# low-gain-radio.net
KiCad netlist of a schematic drawn in EAGLE
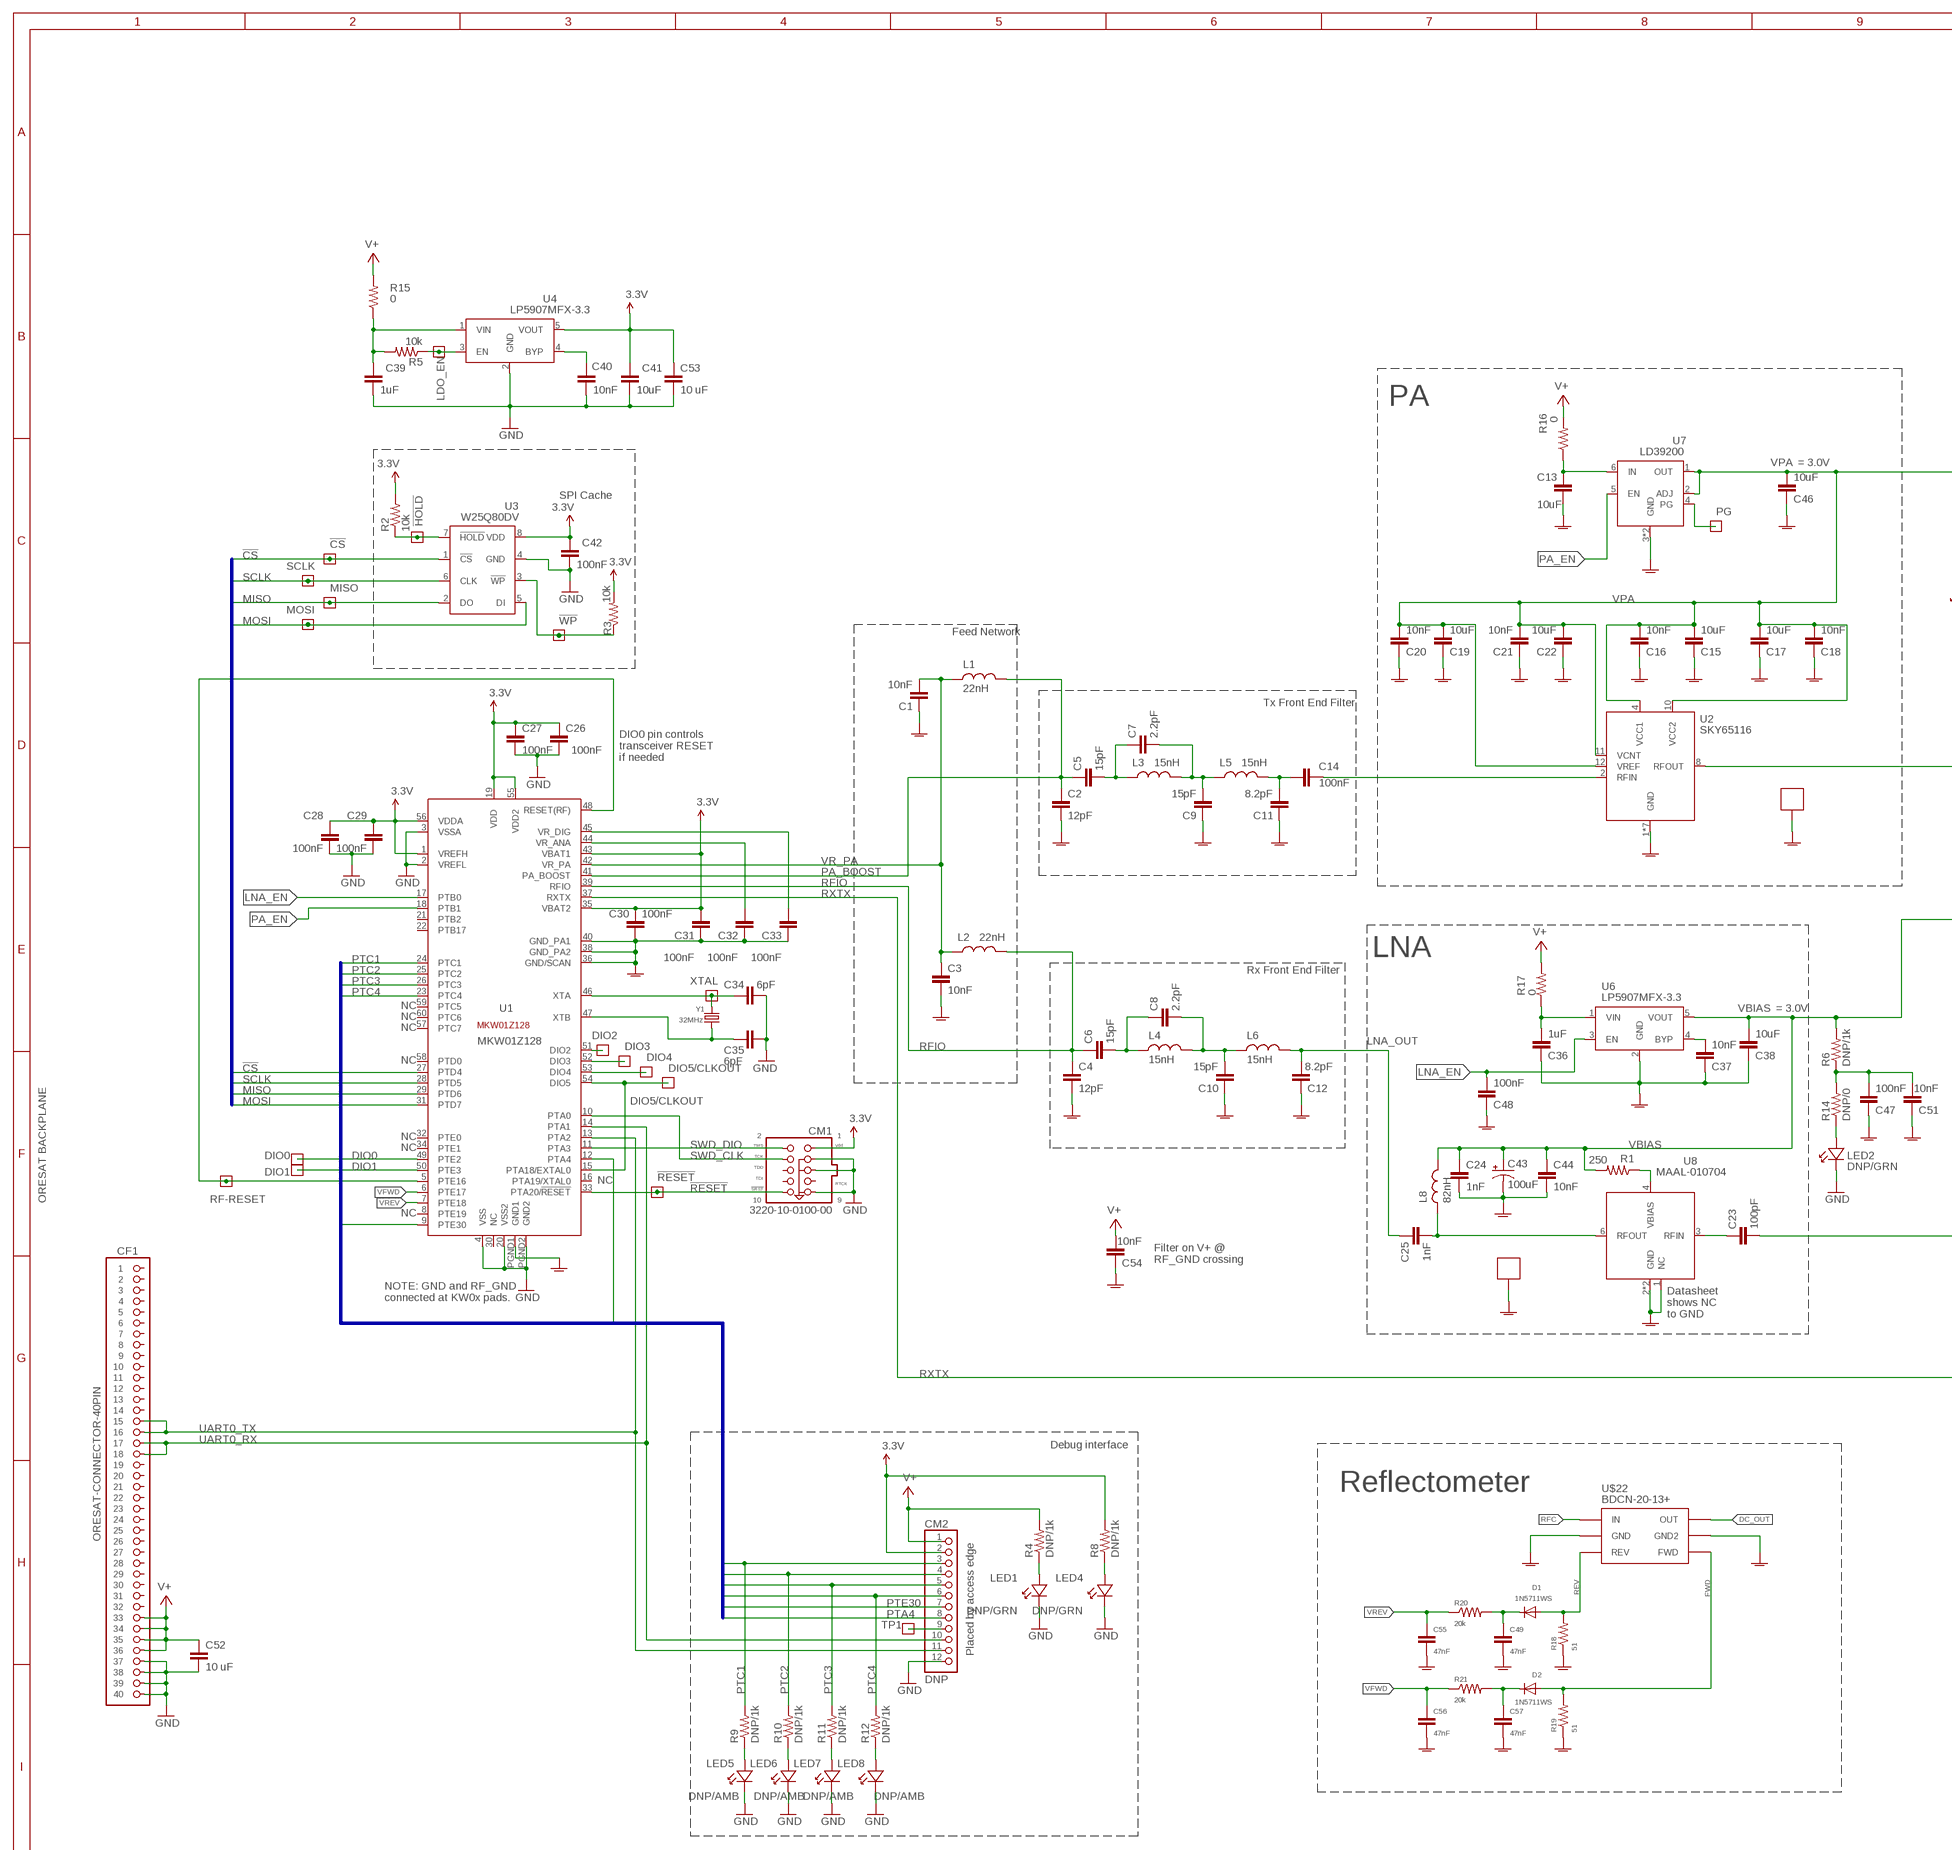
[diagram p0: schematic, sheet 1, part 1 of 2]
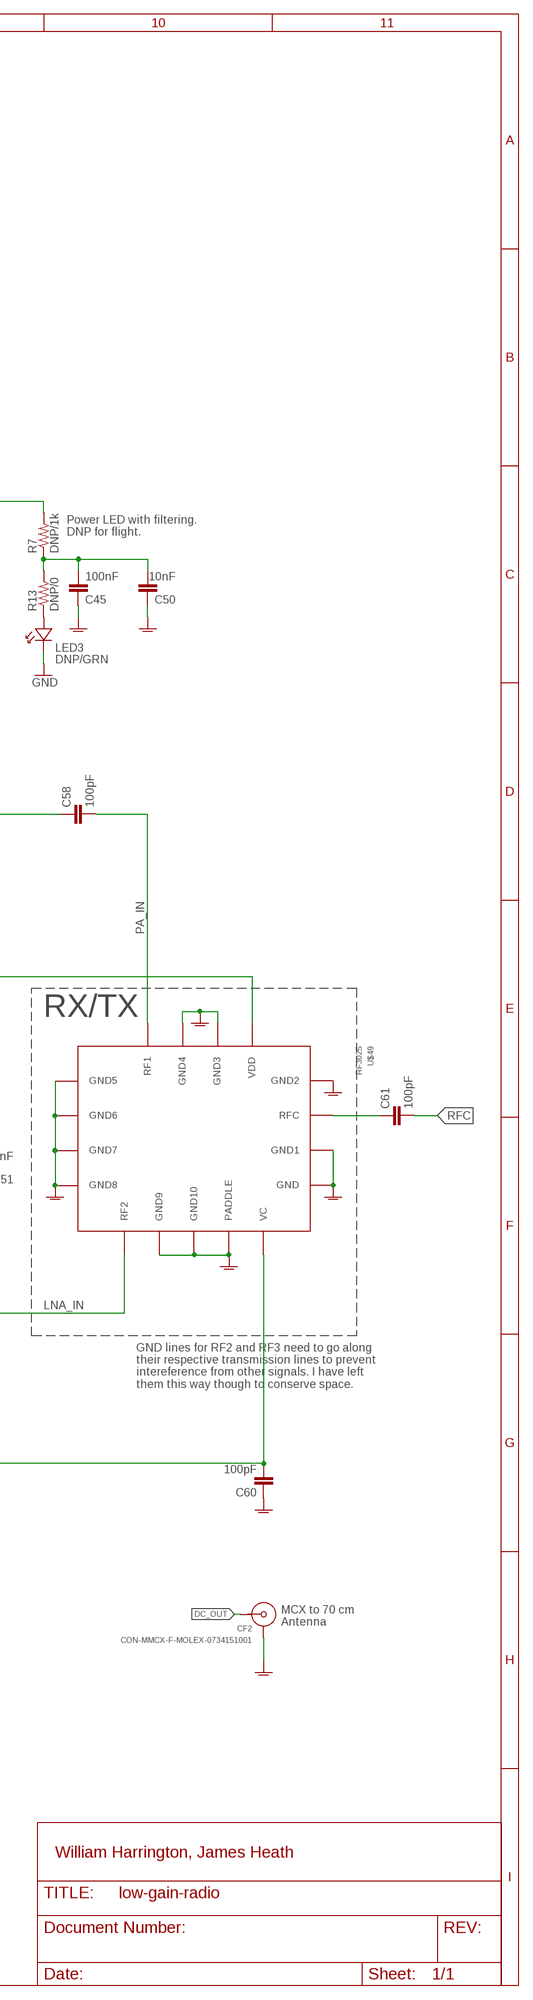
[diagram p1: schematic, sheet 1, part 2 of 2]

(export (version "E")
  (design (tool "Eeschema 10.0.6"))
  (components
    (comp (ref "!CS")
      (value "TEST-POINT")
      (footprint "eagle-import:2MM-TEST-POINT")
      (libsource (lib "eagle-import") (part "TEST-POINT"))
    )
    (comp (ref "!HOLD")
      (value "TEST-POINT")
      (footprint "eagle-import:2MM-TEST-POINT")
      (libsource (lib "eagle-import") (part "TEST-POINT"))
    )
    (comp (ref "!RESET")
      (value "TEST-POINT")
      (footprint "eagle-import:2MM-TEST-POINT")
      (libsource (lib "eagle-import") (part "TEST-POINT"))
    )
    (comp (ref "!WP")
      (value "TEST-POINT")
      (footprint "eagle-import:2MM-TEST-POINT")
      (libsource (lib "eagle-import") (part "TEST-POINT"))
    )
    (comp (ref "C1")
      (value "10nF")
      (footprint "eagle-import:.0603-B-NOSILK")
      (fields (field (name "MFG") "Murata"))
      (libsource (lib "eagle-import") (part "rcl_custom_C-EU0603-B-NOSILK"))
    )
    (comp (ref "C2")
      (value "12pF")
      (footprint "eagle-import:.0603-B-NOSILK")
      (fields (field (name "MFG") "Murata"))
      (libsource (lib "eagle-import") (part "rcl_custom_C-EU0603-B-NOSILK"))
    )
    (comp (ref "C3")
      (value "10nF")
      (footprint "eagle-import:.0603-B-NOSILK")
      (fields (field (name "MFG") "Murata"))
      (libsource (lib "eagle-import") (part "rcl_custom_C-EU0603-B-NOSILK"))
    )
    (comp (ref "C4")
      (value "12pF")
      (footprint "eagle-import:.0603-B-NOSILK")
      (fields (field (name "MFG") "Murata"))
      (libsource (lib "eagle-import") (part "rcl_custom_C-EU0603-B-NOSILK"))
    )
    (comp (ref "C5")
      (value "15pF")
      (footprint "eagle-import:.0603-B-NOSILK")
      (fields (field (name "MFG") "Murata"))
      (libsource (lib "eagle-import") (part "rcl_custom_C-EU0603-B-NOSILK"))
    )
    (comp (ref "C6")
      (value "15pF")
      (footprint "eagle-import:.0603-B-NOSILK")
      (fields (field (name "MFG") "Murata"))
      (libsource (lib "eagle-import") (part "rcl_custom_C-EU0603-B-NOSILK"))
    )
    (comp (ref "C7")
      (value "2.2pF")
      (footprint "eagle-import:.0603-B-NOSILK")
      (fields (field (name "MFG") "Murata"))
      (libsource (lib "eagle-import") (part "rcl_custom_C-EU0603-B-NOSILK"))
    )
    (comp (ref "C8")
      (value "2.2pF")
      (footprint "eagle-import:.0603-B-NOSILK")
      (fields (field (name "MFG") "Murata"))
      (libsource (lib "eagle-import") (part "rcl_custom_C-EU0603-B-NOSILK"))
    )
    (comp (ref "C9")
      (value "15pF")
      (footprint "eagle-import:.0603-B-NOSILK")
      (fields (field (name "MFG") "Murata"))
      (libsource (lib "eagle-import") (part "rcl_custom_C-EU0603-B-NOSILK"))
    )
    (comp (ref "C10")
      (value "15pF")
      (footprint "eagle-import:.0603-B-NOSILK")
      (fields (field (name "MFG") "Murata"))
      (libsource (lib "eagle-import") (part "rcl_custom_C-EU0603-B-NOSILK"))
    )
    (comp (ref "C11")
      (value "8.2pF")
      (footprint "eagle-import:.0603-B-NOSILK")
      (fields (field (name "MFG") "AVX"))
      (libsource (lib "eagle-import") (part "rcl_custom_C-EU0603-B-NOSILK"))
    )
    (comp (ref "C12")
      (value "8.2pF")
      (footprint "eagle-import:.0603-B-NOSILK")
      (fields (field (name "MFG") "AVX"))
      (libsource (lib "eagle-import") (part "rcl_custom_C-EU0603-B-NOSILK"))
    )
    (comp (ref "C13")
      (value "10uF")
      (footprint "eagle-import:.0603-B-NOSILK")
      (fields (field (name "MFG") "Murata"))
      (libsource (lib "eagle-import") (part "rcl_custom_C-EU0603-B-NOSILK"))
    )
    (comp (ref "C14")
      (value "100nF")
      (footprint "eagle-import:.0603-B-NOSILK")
      (fields (field (name "MFG") "AVX"))
      (libsource (lib "eagle-import") (part "rcl_custom_C-EU0603-B-NOSILK"))
    )
    (comp (ref "C15")
      (value "10uF")
      (footprint "eagle-import:.0603-B-NOSILK")
      (fields (field (name "MFG") "Murata"))
      (libsource (lib "eagle-import") (part "rcl_custom_C-EU0603-B-NOSILK"))
    )
    (comp (ref "C16")
      (value "10nF")
      (footprint "eagle-import:.0603-B-NOSILK")
      (fields (field (name "MFG") "Murata"))
      (libsource (lib "eagle-import") (part "rcl_custom_C-EU0603-B-NOSILK"))
    )
    (comp (ref "C17")
      (value "10uF")
      (footprint "eagle-import:.0603-B-NOSILK")
      (fields (field (name "MFG") "Murata"))
      (libsource (lib "eagle-import") (part "rcl_custom_C-EU0603-B-NOSILK"))
    )
    (comp (ref "C18")
      (value "10nF")
      (footprint "eagle-import:.0603-B-NOSILK")
      (fields (field (name "MFG") "Murata"))
      (libsource (lib "eagle-import") (part "rcl_custom_C-EU0603-B-NOSILK"))
    )
    (comp (ref "C19")
      (value "10uF")
      (footprint "eagle-import:.0603-B-NOSILK")
      (fields (field (name "MFG") "Murata"))
      (libsource (lib "eagle-import") (part "rcl_custom_C-EU0603-B-NOSILK"))
    )
    (comp (ref "C20")
      (value "10nF")
      (footprint "eagle-import:.0603-B-NOSILK")
      (fields (field (name "MFG") "Murata"))
      (libsource (lib "eagle-import") (part "rcl_custom_C-EU0603-B-NOSILK"))
    )
    (comp (ref "C21")
      (value "10nF")
      (footprint "eagle-import:.0603-B-NOSILK")
      (fields (field (name "MFG") "Murata"))
      (libsource (lib "eagle-import") (part "rcl_custom_C-EU0603-B-NOSILK"))
    )
    (comp (ref "C22")
      (value "10uF")
      (footprint "eagle-import:.0603-B-NOSILK")
      (fields (field (name "MFG") "Murata"))
      (libsource (lib "eagle-import") (part "rcl_custom_C-EU0603-B-NOSILK"))
    )
    (comp (ref "C23")
      (value "100pF")
      (footprint "eagle-import:.0402-C-NOSILK")
      (fields (field (name "MFG") "Kemet") (field (name "MPN") "CBR04C101F3GAC"))
      (libsource (lib "eagle-import") (part "C-EU0402-C-NOSILK"))
    )
    (comp (ref "C24")
      (value "1nF")
      (footprint "eagle-import:.0402-B-NOSILK")
      (fields (field (name "MFG") "Murata"))
      (libsource (lib "eagle-import") (part "rcl_custom_C-EU0402-B-NOSILK"))
    )
    (comp (ref "C25")
      (value "1nF")
      (footprint "eagle-import:.0402-B-NOSILK")
      (fields (field (name "MFG") "Murata"))
      (libsource (lib "eagle-import") (part "rcl_custom_C-EU0402-B-NOSILK"))
    )
    (comp (ref "C26")
      (value "100nF")
      (footprint "eagle-import:.0603-B-NOSILK")
      (fields (field (name "MFG") "AVX"))
      (libsource (lib "eagle-import") (part "rcl_custom_C-EU0603-B-NOSILK"))
    )
    (comp (ref "C27")
      (value "100nF")
      (footprint "eagle-import:.0603-B-NOSILK")
      (fields (field (name "MFG") "AVX"))
      (libsource (lib "eagle-import") (part "rcl_custom_C-EU0603-B-NOSILK"))
    )
    (comp (ref "C28")
      (value "100nF")
      (footprint "eagle-import:.0603-B-NOSILK")
      (fields (field (name "MFG") "AVX"))
      (libsource (lib "eagle-import") (part "rcl_custom_C-EU0603-B-NOSILK"))
    )
    (comp (ref "C29")
      (value "100nF")
      (footprint "eagle-import:.0603-B-NOSILK")
      (fields (field (name "MFG") "AVX"))
      (libsource (lib "eagle-import") (part "rcl_custom_C-EU0603-B-NOSILK"))
    )
    (comp (ref "C30")
      (value "100nF")
      (footprint "eagle-import:.0603-B-NOSILK")
      (fields (field (name "MFG") "AVX"))
      (libsource (lib "eagle-import") (part "rcl_custom_C-EU0603-B-NOSILK"))
    )
    (comp (ref "C31")
      (value "100nF")
      (footprint "eagle-import:.0603-B-NOSILK")
      (fields (field (name "MFG") "AVX"))
      (libsource (lib "eagle-import") (part "rcl_custom_C-EU0603-B-NOSILK"))
    )
    (comp (ref "C32")
      (value "100nF")
      (footprint "eagle-import:.0603-B-NOSILK")
      (fields (field (name "MFG") "AVX"))
      (libsource (lib "eagle-import") (part "rcl_custom_C-EU0603-B-NOSILK"))
    )
    (comp (ref "C33")
      (value "100nF")
      (footprint "eagle-import:.0603-B-NOSILK")
      (fields (field (name "MFG") "AVX"))
      (libsource (lib "eagle-import") (part "rcl_custom_C-EU0603-B-NOSILK"))
    )
    (comp (ref "C34")
      (value "6pF")
      (footprint "eagle-import:.0603-B-NOSILK")
      (fields (field (name "MFG") "Murata"))
      (libsource (lib "eagle-import") (part "rcl_custom_C-EU0603-B-NOSILK"))
    )
    (comp (ref "C35")
      (value "6pF")
      (footprint "eagle-import:.0603-B-NOSILK")
      (fields (field (name "MFG") "Murata"))
      (libsource (lib "eagle-import") (part "rcl_custom_C-EU0603-B-NOSILK"))
    )
    (comp (ref "C36")
      (value "1uF")
      (footprint "eagle-import:.0603-B-NOSILK")
      (fields (field (name "MFG") "Murata"))
      (libsource (lib "eagle-import") (part "rcl_custom_C-EU0603-B-NOSILK"))
    )
    (comp (ref "C37")
      (value "10nF")
      (footprint "eagle-import:.0603-B-NOSILK")
      (fields (field (name "MFG") "Murata"))
      (libsource (lib "eagle-import") (part "rcl_custom_C-EU0603-B-NOSILK"))
    )
    (comp (ref "C38")
      (value "10uF")
      (footprint "eagle-import:.0603-B-NOSILK")
      (fields (field (name "MFG") "Murata"))
      (libsource (lib "eagle-import") (part "rcl_custom_C-EU0603-B-NOSILK"))
    )
    (comp (ref "C39")
      (value "1uF")
      (footprint "eagle-import:.0603-B-NOSILK")
      (fields (field (name "MFG") "Murata"))
      (libsource (lib "eagle-import") (part "rcl_custom_C-EU0603-B-NOSILK"))
    )
    (comp (ref "C40")
      (value "10nF")
      (footprint "eagle-import:.0603-B-NOSILK")
      (fields (field (name "MFG") "Murata"))
      (libsource (lib "eagle-import") (part "rcl_custom_C-EU0603-B-NOSILK"))
    )
    (comp (ref "C41")
      (value "10uF")
      (footprint "eagle-import:.0603-B-NOSILK")
      (fields (field (name "MFG") "Murata"))
      (libsource (lib "eagle-import") (part "rcl_custom_C-EU0603-B-NOSILK"))
    )
    (comp (ref "C42")
      (value "100nF")
      (footprint "eagle-import:.0603-B-NOSILK")
      (fields (field (name "MFG") "AVX"))
      (libsource (lib "eagle-import") (part "rcl_custom_C-EU0603-B-NOSILK"))
    )
    (comp (ref "C43")
      (value "100uF")
      (footprint "eagle-import:CT6032")
      (fields (field (name "MFG") "AVX"))
      (libsource (lib "eagle-import") (part "CPOL-USCT6032"))
    )
    (comp (ref "C44")
      (value "10nF")
      (footprint "eagle-import:.0402-B-NOSILK")
      (fields (field (name "MFG") "Murata"))
      (libsource (lib "eagle-import") (part "rcl_custom_C-EU0402-B-NOSILK"))
    )
    (comp (ref "C45")
      (value "100nF")
      (footprint "eagle-import:.0603-B-NOSILK")
      (fields (field (name "MFG") "AVX"))
      (libsource (lib "eagle-import") (part "rcl_custom_C-EU0603-B-NOSILK"))
    )
    (comp (ref "C46")
      (value "10uF")
      (footprint "eagle-import:.0603-B-NOSILK")
      (fields (field (name "MFG") "Murata"))
      (libsource (lib "eagle-import") (part "rcl_custom_C-EU0603-B-NOSILK"))
    )
    (comp (ref "C47")
      (value "100nF")
      (footprint "eagle-import:.0603-B-NOSILK")
      (fields (field (name "MFG") "AVX"))
      (libsource (lib "eagle-import") (part "rcl_custom_C-EU0603-B-NOSILK"))
    )
    (comp (ref "C48")
      (value "100nF")
      (footprint "eagle-import:.0603-B-NOSILK")
      (fields (field (name "MFG") "AVX"))
      (libsource (lib "eagle-import") (part "rcl_custom_C-EU0603-B-NOSILK"))
    )
    (comp (ref "C49")
      (value "47nF")
      (footprint "eagle-import:.0402-C-NOSILK")
      (fields (field (name "MFG") "Taiyo Yuden") (field (name "MPN") "LMK105SD472KV-F"))
      (libsource (lib "eagle-import") (part "C-EU0402-C-NOSILK"))
    )
    (comp (ref "C50")
      (value "10nF")
      (footprint "eagle-import:.0402-B-NOSILK")
      (fields (field (name "MFG") "Murata"))
      (libsource (lib "eagle-import") (part "rcl_custom_C-EU0402-B-NOSILK"))
    )
    (comp (ref "C51")
      (value "10nF")
      (footprint "eagle-import:.0402-B-NOSILK")
      (fields (field (name "MFG") "Murata"))
      (libsource (lib "eagle-import") (part "rcl_custom_C-EU0402-B-NOSILK"))
    )
    (comp (ref "C52")
      (value "10 uF")
      (footprint "eagle-import:.0805-B-NOSILK")
      (libsource (lib "eagle-import") (part "rcl_custom_C-EU0805-B-NOSILK"))
    )
    (comp (ref "C53")
      (value "10 uF")
      (footprint "eagle-import:.0805-B-NOSILK")
      (fields (field (name "MFG") "Murata"))
      (libsource (lib "eagle-import") (part "rcl_custom_C-EU0805-B-NOSILK"))
    )
    (comp (ref "C54")
      (value "10nF")
      (footprint "eagle-import:.0402-B-NOSILK")
      (fields (field (name "MFG") "Murata"))
      (libsource (lib "eagle-import") (part "rcl_custom_C-EU0402-B-NOSILK"))
    )
    (comp (ref "C55")
      (value "47nF")
      (footprint "eagle-import:.0402-C-NOSILK")
      (fields (field (name "MFG") "Taiyo Yuden") (field (name "MPN") "LMK105SD472KV-F"))
      (libsource (lib "eagle-import") (part "C-EU0402-C-NOSILK"))
    )
    (comp (ref "C56")
      (value "47nF")
      (footprint "eagle-import:.0402-C-NOSILK")
      (fields (field (name "MFG") "Taiyo Yuden") (field (name "MPN") "LMK105SD472KV-F"))
      (libsource (lib "eagle-import") (part "C-EU0402-C-NOSILK"))
    )
    (comp (ref "C57")
      (value "47nF")
      (footprint "eagle-import:.0402-C-NOSILK")
      (fields (field (name "MFG") "Taiyo Yuden") (field (name "MPN") "LMK105SD472KV-F"))
      (libsource (lib "eagle-import") (part "C-EU0402-C-NOSILK"))
    )
    (comp (ref "C58")
      (value "100pF")
      (footprint "eagle-import:.0402-C-NOSILK")
      (fields (field (name "MFG") "Kemet") (field (name "MPN") "CBR04C101F3GAC"))
      (libsource (lib "eagle-import") (part "C-EU0402-C-NOSILK"))
    )
    (comp (ref "C60")
      (value "100pF")
      (footprint "eagle-import:.0402-C-NOSILK")
      (fields (field (name "MFG") "Kemet") (field (name "MPN") "CBR04C101F3GAC"))
      (libsource (lib "eagle-import") (part "C-EU0402-C-NOSILK"))
    )
    (comp (ref "C61")
      (value "100pF")
      (footprint "eagle-import:.0402-C-NOSILK")
      (fields (field (name "MFG") "Kemet") (field (name "MPN") "CBR04C101F3GAC"))
      (libsource (lib "eagle-import") (part "C-EU0402-C-NOSILK"))
    )
    (comp (ref "CF1")
      (value "ORESAT-CONNECTOR-40PIN")
      (footprint "eagle-import:HARWIN-ARCHER-M50-3202045")
      (libsource (lib "eagle-import") (part "ORESAT-CONNECTOR-40PIN"))
    )
    (comp (ref "CF2")
      (value "CON-MMCX-F-MOLEX-0734151001")
      (footprint "eagle-import:CON-MMCX-F-MOLEX-0734151001")
      (libsource (lib "eagle-import") (part "CON-MMCX-F-MOLEX-0734151001"))
    )
    (comp (ref "CM1")
      (value "3220-10-0100-00")
      (footprint "eagle-import:PINHEADER-2X5-0.05+POL+SILK")
      (fields (field (name "MFG") "CNC Tech"))
      (libsource (lib "eagle-import") (part "JTAG_ARM-10-50MIL"))
    )
    (comp (ref "CM2")
      (value "DNP")
      (footprint "eagle-import:1X12")
      (libsource (lib "eagle-import") (part "PINHD-1X12"))
    )
    (comp (ref "D1")
      (value "1N5711WS")
      (footprint "eagle-import:SOD-323")
      (fields (field (name "MFG") "Diodes Incorporated"))
      (libsource (lib "eagle-import") (part "DIODESOD-323"))
    )
    (comp (ref "D2")
      (value "1N5711WS")
      (footprint "eagle-import:SOD-323")
      (fields (field (name "MFG") "Diodes Incorporated"))
      (libsource (lib "eagle-import") (part "DIODESOD-323"))
    )
    (comp (ref "DIO0")
      (value "TEST-POINT")
      (footprint "eagle-import:2MM-TEST-POINT")
      (libsource (lib "eagle-import") (part "TEST-POINT"))
    )
    (comp (ref "DIO1")
      (value "TEST-POINT")
      (footprint "eagle-import:2MM-TEST-POINT")
      (libsource (lib "eagle-import") (part "TEST-POINT"))
    )
    (comp (ref "DIO2")
      (value "TEST-POINT")
      (footprint "eagle-import:2MM-TEST-POINT")
      (libsource (lib "eagle-import") (part "TEST-POINT"))
    )
    (comp (ref "DIO3")
      (value "TEST-POINT")
      (footprint "eagle-import:2MM-TEST-POINT")
      (libsource (lib "eagle-import") (part "TEST-POINT"))
    )
    (comp (ref "DIO4")
      (value "TEST-POINT")
      (footprint "eagle-import:2MM-TEST-POINT")
      (libsource (lib "eagle-import") (part "TEST-POINT"))
    )
    (comp (ref "DIO5/CLKOUT")
      (value "TEST-POINT")
      (footprint "eagle-import:2MM-TEST-POINT")
      (libsource (lib "eagle-import") (part "TEST-POINT"))
    )
    (comp (ref "L1")
      (value "22nH")
      (footprint "eagle-import:.0603-B-NOSILK@1")
      (fields (field (name "MFG") "Murata"))
      (libsource (lib "eagle-import") (part "L-US0603-B-NOSILK"))
    )
    (comp (ref "L2")
      (value "22nH")
      (footprint "eagle-import:.0603-B-NOSILK@1")
      (fields (field (name "MFG") "Murata"))
      (libsource (lib "eagle-import") (part "L-US0603-B-NOSILK"))
    )
    (comp (ref "L3")
      (value "15nH")
      (footprint "eagle-import:.0603-B-NOSILK@1")
      (fields (field (name "MFG") "Murata"))
      (libsource (lib "eagle-import") (part "L-US0603-B-NOSILK"))
    )
    (comp (ref "L4")
      (value "15nH")
      (footprint "eagle-import:.0603-B-NOSILK@1")
      (fields (field (name "MFG") "Murata"))
      (libsource (lib "eagle-import") (part "L-US0603-B-NOSILK"))
    )
    (comp (ref "L5")
      (value "15nH")
      (footprint "eagle-import:.0603-B-NOSILK@1")
      (fields (field (name "MFG") "Murata"))
      (libsource (lib "eagle-import") (part "L-US0603-B-NOSILK"))
    )
    (comp (ref "L6")
      (value "15nH")
      (footprint "eagle-import:.0603-B-NOSILK@1")
      (fields (field (name "MFG") "Murata"))
      (libsource (lib "eagle-import") (part "L-US0603-B-NOSILK"))
    )
    (comp (ref "L8")
      (value "82nH")
      (footprint "eagle-import:.0603-B-NOSILK@1")
      (fields (field (name "MFG") "Murata"))
      (libsource (lib "eagle-import") (part "L-US0603-B-NOSILK"))
    )
    (comp (ref "LDO_EN")
      (value "TEST-POINT")
      (footprint "eagle-import:2MM-TEST-POINT")
      (libsource (lib "eagle-import") (part "TEST-POINT"))
    )
    (comp (ref "LED1")
      (value "DNP/GRN")
      (footprint "eagle-import:LED-0603")
      (fields (field (name "MFG") "Lite-On Inc."))
      (libsource (lib "eagle-import") (part "LED-0603"))
    )
    (comp (ref "LED2")
      (value "DNP/GRN")
      (footprint "eagle-import:LED-0603")
      (fields (field (name "MFG") "Lite-On Inc."))
      (libsource (lib "eagle-import") (part "LED-0603"))
    )
    (comp (ref "LED3")
      (value "DNP/GRN")
      (footprint "eagle-import:LED-0603")
      (fields (field (name "MFG") "Lite-On Inc."))
      (libsource (lib "eagle-import") (part "LED-0603"))
    )
    (comp (ref "LED4")
      (value "DNP/GRN")
      (footprint "eagle-import:LED-0603")
      (fields (field (name "MFG") "Lite-On Inc."))
      (libsource (lib "eagle-import") (part "LED-0603"))
    )
    (comp (ref "LED5")
      (value "DNP/AMB")
      (footprint "eagle-import:LED-0603")
      (fields (field (name "MFG") "Lite-On Inc."))
      (libsource (lib "eagle-import") (part "LED-0603"))
    )
    (comp (ref "LED6")
      (value "DNP/AMB")
      (footprint "eagle-import:LED-0603")
      (fields (field (name "MFG") "Lite-On Inc."))
      (libsource (lib "eagle-import") (part "LED-0603"))
    )
    (comp (ref "LED7")
      (value "DNP/AMB")
      (footprint "eagle-import:LED-0603")
      (fields (field (name "MFG") "Lite-On Inc."))
      (libsource (lib "eagle-import") (part "LED-0603"))
    )
    (comp (ref "LED8")
      (value "DNP/AMB")
      (footprint "eagle-import:LED-0603")
      (fields (field (name "MFG") "Lite-On Inc."))
      (libsource (lib "eagle-import") (part "LED-0603"))
    )
    (comp (ref "MISO")
      (value "TEST-POINT")
      (footprint "eagle-import:2MM-TEST-POINT")
      (libsource (lib "eagle-import") (part "TEST-POINT"))
    )
    (comp (ref "MOSI")
      (value "TEST-POINT")
      (footprint "eagle-import:2MM-TEST-POINT")
      (libsource (lib "eagle-import") (part "TEST-POINT"))
    )
    (comp (ref "PG")
      (value "TEST-POINT")
      (footprint "eagle-import:2MM-TEST-POINT")
      (libsource (lib "eagle-import") (part "TEST-POINT"))
    )
    (comp (ref "R1")
      (value "250")
      (footprint "eagle-import:.0603-B-NOSILK@1")
      (fields (field (name "MFG") "Samsung"))
      (libsource (lib "eagle-import") (part "rcl_custom_R-US_0603-B-NOSILK"))
    )
    (comp (ref "R2")
      (value "10k")
      (footprint "eagle-import:.0603-B-NOSILK@1")
      (fields (field (name "MFG") "Yageo"))
      (libsource (lib "eagle-import") (part "rcl_custom_R-US_0603-B-NOSILK"))
    )
    (comp (ref "R3")
      (value "10k")
      (footprint "eagle-import:.0603-B-NOSILK@1")
      (fields (field (name "MFG") "Yageo"))
      (libsource (lib "eagle-import") (part "rcl_custom_R-US_0603-B-NOSILK"))
    )
    (comp (ref "R4")
      (value "DNP/1k")
      (footprint "eagle-import:.0603-B-NOSILK@1")
      (fields (field (name "MFG") "Yageo"))
      (libsource (lib "eagle-import") (part "rcl_custom_R-US_0603-B-NOSILK"))
    )
    (comp (ref "R5")
      (value "10k")
      (footprint "eagle-import:.0603-B-NOSILK@1")
      (fields (field (name "MFG") "Yageo"))
      (libsource (lib "eagle-import") (part "rcl_custom_R-US_0603-B-NOSILK"))
    )
    (comp (ref "R6")
      (value "DNP/1k")
      (footprint "eagle-import:.0603-B-NOSILK@1")
      (fields (field (name "MFG") "Yageo"))
      (libsource (lib "eagle-import") (part "rcl_custom_R-US_0603-B-NOSILK"))
    )
    (comp (ref "R7")
      (value "DNP/1k")
      (footprint "eagle-import:.0603-B-NOSILK@1")
      (fields (field (name "MFG") "Yageo"))
      (libsource (lib "eagle-import") (part "rcl_custom_R-US_0603-B-NOSILK"))
    )
    (comp (ref "R8")
      (value "DNP/1k")
      (footprint "eagle-import:.0603-B-NOSILK@1")
      (fields (field (name "MFG") "Yageo"))
      (libsource (lib "eagle-import") (part "rcl_custom_R-US_0603-B-NOSILK"))
    )
    (comp (ref "R9")
      (value "DNP/1k")
      (footprint "eagle-import:.0603-B-NOSILK@1")
      (fields (field (name "MFG") "Yageo"))
      (libsource (lib "eagle-import") (part "rcl_custom_R-US_0603-B-NOSILK"))
    )
    (comp (ref "R10")
      (value "DNP/1k")
      (footprint "eagle-import:.0603-B-NOSILK@1")
      (fields (field (name "MFG") "Yageo"))
      (libsource (lib "eagle-import") (part "rcl_custom_R-US_0603-B-NOSILK"))
    )
    (comp (ref "R11")
      (value "DNP/1k")
      (footprint "eagle-import:.0603-B-NOSILK@1")
      (fields (field (name "MFG") "Yageo"))
      (libsource (lib "eagle-import") (part "rcl_custom_R-US_0603-B-NOSILK"))
    )
    (comp (ref "R12")
      (value "DNP/1k")
      (footprint "eagle-import:.0603-B-NOSILK@1")
      (fields (field (name "MFG") "Yageo"))
      (libsource (lib "eagle-import") (part "rcl_custom_R-US_0603-B-NOSILK"))
    )
    (comp (ref "R13")
      (value "DNP/0")
      (footprint "eagle-import:.0603-B-NOSILK@1")
      (fields (field (name "MFG") "Yageo"))
      (libsource (lib "eagle-import") (part "rcl_custom_R-US_0603-B-NOSILK"))
    )
    (comp (ref "R14")
      (value "DNP/0")
      (footprint "eagle-import:.0603-B-NOSILK@1")
      (fields (field (name "MFG") "Yageo"))
      (libsource (lib "eagle-import") (part "rcl_custom_R-US_0603-B-NOSILK"))
    )
    (comp (ref "R15")
      (value "0")
      (footprint "eagle-import:.0805-C-NOSILK$1")
      (fields (field (name "MFG") "Yageo") (field (name "MPN") "RC0805JR-070RL"))
      (libsource (lib "eagle-import") (part "R-US_0805-C-NOSILK"))
    )
    (comp (ref "R16")
      (value "0")
      (footprint "eagle-import:.0805-C-NOSILK$1")
      (fields (field (name "MFG") "Yageo") (field (name "MPN") "RC0805JR-070RL"))
      (libsource (lib "eagle-import") (part "R-US_0805-C-NOSILK"))
    )
    (comp (ref "R17")
      (value "0")
      (footprint "eagle-import:.0805-C-NOSILK$1")
      (fields (field (name "MFG") "Yageo") (field (name "MPN") "RC0805JR-070RL"))
      (libsource (lib "eagle-import") (part "R-US_0805-C-NOSILK"))
    )
    (comp (ref "R18")
      (value "51")
      (footprint "eagle-import:.0402-C-NOSILK$1")
      (fields (field (name "MFG") "Yageo") (field (name "MPN") "RC0402FR-0751RL"))
      (libsource (lib "eagle-import") (part "R-US_0402-C-NOSILK"))
    )
    (comp (ref "R19")
      (value "51")
      (footprint "eagle-import:.0402-C-NOSILK$1")
      (fields (field (name "MFG") "Yageo") (field (name "MPN") "RC0402FR-0751RL"))
      (libsource (lib "eagle-import") (part "R-US_0402-C-NOSILK"))
    )
    (comp (ref "R20")
      (value "20k")
      (footprint "eagle-import:.0402-C-NOSILK$1")
      (fields (field (name "MFG") "Yageo") (field (name "MPN") "RT0402BRD0721KL"))
      (libsource (lib "eagle-import") (part "R-US_0402-C-NOSILK"))
    )
    (comp (ref "R21")
      (value "20k")
      (footprint "eagle-import:.0402-C-NOSILK$1")
      (fields (field (name "MFG") "Yageo") (field (name "MPN") "RT0402BRD0721KL"))
      (libsource (lib "eagle-import") (part "R-US_0402-C-NOSILK"))
    )
    (comp (ref "RF-RESET")
      (value "TEST-POINT")
      (footprint "eagle-import:2MM-TEST-POINT")
      (libsource (lib "eagle-import") (part "TEST-POINT"))
    )
    (comp (ref "SCLK")
      (value "TEST-POINT")
      (footprint "eagle-import:2MM-TEST-POINT")
      (libsource (lib "eagle-import") (part "TEST-POINT"))
    )
    (comp (ref "SH1")
      (value "BMI-S-202-SHIELD")
      (footprint "eagle-import:BMI-S-202")
      (libsource (lib "eagle-import") (part "BMI-S-202-SHIELD"))
    )
    (comp (ref "SH2")
      (value "BMI-S-202-SHIELD")
      (footprint "eagle-import:BMI-S-202")
      (libsource (lib "eagle-import") (part "BMI-S-202-SHIELD"))
    )
    (comp (ref "TP1")
      (value "TEST-POINT")
      (footprint "eagle-import:2MM-TEST-POINT")
      (libsource (lib "eagle-import") (part "TEST-POINT"))
    )
    (comp (ref "U$22")
      (value "BDCN-20-13+")
      (footprint "eagle-import:FV1206-1")
      (fields (field (name "MFG") "Mini-Circuits"))
      (libsource (lib "eagle-import") (part "BDCN-20-13+"))
    )
    (comp (ref "U$49")
      (value "RF3025")
      (footprint "eagle-import:QFN-16_3MMX3MM")
      (fields (field (name "MFG") "RFMD") (field (name "MPN") "RF3025TR7"))
      (libsource (lib "eagle-import") (part "RF3025"))
    )
    (comp (ref "U1")
      (value "MKW01Z128")
      (footprint "eagle-import:MKW01Z128")
      (fields (field (name "MPN") "MKW01Z128CHN"))
      (libsource (lib "eagle-import") (part "MKW01Z128"))
    )
    (comp (ref "U2")
      (value "SKY65116")
      (footprint "eagle-import:SKY65116")
      (libsource (lib "eagle-import") (part "SKY65116"))
    )
    (comp (ref "U3")
      (value "W25Q80DV")
      (footprint "eagle-import:W25Q80DV")
      (fields (field (name "MFG") "Winbond Electronics"))
      (libsource (lib "eagle-import") (part "W25Q80DV"))
    )
    (comp (ref "U4")
      (value "LP5907MFX-3.3")
      (footprint "eagle-import:SOT23-5")
      (libsource (lib "eagle-import") (part "AAT3215"))
    )
    (comp (ref "U6")
      (value "LP5907MFX-3.3")
      (footprint "eagle-import:SOT23-5")
      (libsource (lib "eagle-import") (part "AAT3215"))
    )
    (comp (ref "U7")
      (value "LD39200")
      (footprint "eagle-import:LD39200")
      (fields (field (name "MFG") "STMicroelectronics"))
      (libsource (lib "eagle-import") (part "LD39200"))
    )
    (comp (ref "U8")
      (value "MAAL-010704")
      (footprint "eagle-import:SOT-363")
      (libsource (lib "eagle-import") (part "MAAL-010704"))
    )
    (comp (ref "XTAL")
      (value "TEST-POINT")
      (footprint "eagle-import:2MM-TEST-POINT")
      (libsource (lib "eagle-import") (part "TEST-POINT"))
    )
    (comp (ref "Y1")
      (value "32MHz")
      (footprint "eagle-import:CRYSTAL_2.5X2")
      (fields (field (name "MPN") "FA20H 32.0000MF12Y-W3"))
      (libsource (lib "eagle-import") (part "CRYSTAL2.5X2.0MM"))
    )
  )
  (nets
    (net (code "1") (name "/DIO0") (class "Default")
      (node (ref "DIO0") (pin "1") (pinfunction "1_1") (pintype "passive"))
      (node (ref "U1") (pin "49") (pinfunction "PTE2_49") (pintype "bidirectional"))
    )
    (net (code "2") (name "/DIO1") (class "Default")
      (node (ref "DIO1") (pin "1") (pinfunction "1_1") (pintype "passive"))
      (node (ref "U1") (pin "50") (pinfunction "PTE3_50") (pintype "bidirectional"))
    )
    (net (code "3") (name "/DIO5{slash}CLKOUT") (class "Default")
      (node (ref "DIO5/CLKOUT") (pin "1") (pinfunction "1_1") (pintype "passive"))
      (node (ref "U1") (pin "15") (pinfunction "PTA18/EXTAL0_15") (pintype "bidirectional"))
      (node (ref "U1") (pin "54") (pinfunction "DIO5_54") (pintype "bidirectional"))
    )
    (net (code "4") (name "/FWD") (class "Default")
      (node (ref "D2") (pin "A") (pinfunction "A_A") (pintype "passive"))
      (node (ref "R19") (pin "2") (pinfunction "2_2") (pintype "passive"))
      (node (ref "U$22") (pin "FWD") (pinfunction "FWD_FWD") (pintype "bidirectional"))
    )
    (net (code "5") (name "/LNA_IN") (class "Default")
      (node (ref "C23") (pin "2") (pinfunction "2_2") (pintype "passive"))
      (node (ref "U$49") (pin "RF2") (pinfunction "RF2_RF2") (pintype "bidirectional"))
    )
    (net (code "6") (name "/LNA_OUT") (class "Default")
      (node (ref "C12") (pin "2") (pinfunction "2_2") (pintype "passive"))
      (node (ref "C25") (pin "1") (pinfunction "1_1") (pintype "passive"))
      (node (ref "L6") (pin "2") (pinfunction "2_2") (pintype "passive"))
    )
    (net (code "7") (name "/MISO") (class "Default")
      (node (ref "MISO") (pin "1") (pinfunction "1_1") (pintype "passive"))
      (node (ref "U1") (pin "29") (pinfunction "PTD6_29") (pintype "bidirectional"))
      (node (ref "U3") (pin "2") (pinfunction "DO_2") (pintype "output"))
    )
    (net (code "8") (name "/MOSI") (class "Default")
      (node (ref "MOSI") (pin "1") (pinfunction "1_1") (pintype "passive"))
      (node (ref "U1") (pin "31") (pinfunction "PTD7_31") (pintype "bidirectional"))
      (node (ref "U3") (pin "5") (pinfunction "DI_5") (pintype "input"))
    )
    (net (code "9") (name "/PA_BOOST") (class "Default")
      (node (ref "C2") (pin "1") (pinfunction "1_1") (pintype "passive"))
      (node (ref "C5") (pin "1") (pinfunction "1_1") (pintype "passive"))
      (node (ref "L1") (pin "2") (pinfunction "2_2") (pintype "passive"))
      (node (ref "U1") (pin "41") (pinfunction "PA_BOOST_41") (pintype "output"))
    )
    (net (code "10") (name "/PA_IN") (class "Default")
      (node (ref "C58") (pin "2") (pinfunction "2_2") (pintype "passive"))
      (node (ref "U$49") (pin "RF1") (pinfunction "RF1_RF1") (pintype "bidirectional"))
    )
    (net (code "11") (name "/PTA4") (class "Default")
      (node (ref "CM2") (pin "8") (pinfunction "8_8") (pintype "passive"))
      (node (ref "U1") (pin "12") (pinfunction "PTA4_12") (pintype "bidirectional"))
    )
    (net (code "12") (name "/PTC1") (class "Default")
      (node (ref "CM2") (pin "3") (pinfunction "3_3") (pintype "passive"))
      (node (ref "R9") (pin "2") (pinfunction "2_2") (pintype "passive"))
      (node (ref "U1") (pin "24") (pinfunction "PTC1_24") (pintype "bidirectional"))
    )
    (net (code "13") (name "/PTC2") (class "Default")
      (node (ref "CM2") (pin "4") (pinfunction "4_4") (pintype "passive"))
      (node (ref "R10") (pin "2") (pinfunction "2_2") (pintype "passive"))
      (node (ref "U1") (pin "25") (pinfunction "PTC2_25") (pintype "bidirectional"))
    )
    (net (code "14") (name "/PTC3") (class "Default")
      (node (ref "CM2") (pin "5") (pinfunction "5_5") (pintype "passive"))
      (node (ref "R11") (pin "2") (pinfunction "2_2") (pintype "passive"))
      (node (ref "U1") (pin "26") (pinfunction "PTC3_26") (pintype "bidirectional"))
    )
    (net (code "15") (name "/PTC4") (class "Default")
      (node (ref "CM2") (pin "6") (pinfunction "6_6") (pintype "passive"))
      (node (ref "R12") (pin "2") (pinfunction "2_2") (pintype "passive"))
      (node (ref "U1") (pin "23") (pinfunction "PTC4_23") (pintype "bidirectional"))
    )
    (net (code "16") (name "/PTE30") (class "Default")
      (node (ref "CM2") (pin "7") (pinfunction "7_7") (pintype "passive"))
      (node (ref "U1") (pin "9") (pinfunction "PTE30_9") (pintype "bidirectional"))
    )
    (net (code "17") (name "/REV") (class "Default")
      (node (ref "D1") (pin "A") (pinfunction "A_A") (pintype "passive"))
      (node (ref "R18") (pin "2") (pinfunction "2_2") (pintype "passive"))
      (node (ref "U$22") (pin "REV") (pinfunction "REV_REV") (pintype "bidirectional"))
    )
    (net (code "18") (name "/RFIO") (class "Default")
      (node (ref "C4") (pin "1") (pinfunction "1_1") (pintype "passive"))
      (node (ref "C6") (pin "1") (pinfunction "1_1") (pintype "passive"))
      (node (ref "L2") (pin "2") (pinfunction "2_2") (pintype "passive"))
      (node (ref "U1") (pin "39") (pinfunction "RFIO_39") (pintype "bidirectional"))
    )
    (net (code "19") (name "/RXTX") (class "Default")
      (node (ref "C60") (pin "2") (pinfunction "2_2") (pintype "passive"))
      (node (ref "U$49") (pin "VC") (pinfunction "VC_VC") (pintype "bidirectional"))
      (node (ref "U1") (pin "37") (pinfunction "RXTX_37") (pintype "output"))
    )
    (net (code "20") (name "/SCLK") (class "Default")
      (node (ref "SCLK") (pin "1") (pinfunction "1_1") (pintype "passive"))
      (node (ref "U1") (pin "28") (pinfunction "PTD5_28") (pintype "bidirectional"))
      (node (ref "U3") (pin "6") (pinfunction "CLK_6") (pintype "input"))
    )
    (net (code "21") (name "/SWD_CLK") (class "Default")
      (node (ref "CM1") (pin "4") (pinfunction "TCK_4") (pintype "passive"))
      (node (ref "U1") (pin "10") (pinfunction "PTA0_10") (pintype "bidirectional"))
    )
    (net (code "22") (name "/SWD_DIO") (class "Default")
      (node (ref "CM1") (pin "2") (pinfunction "TMS_2") (pintype "passive"))
      (node (ref "U1") (pin "11") (pinfunction "PTA3_11") (pintype "bidirectional"))
    )
    (net (code "23") (name "/UART0_RX") (class "Default")
      (node (ref "CF1") (pin "P$17") (pinfunction "17_P$17") (pintype "passive"))
      (node (ref "CF1") (pin "P$18") (pinfunction "18_P$18") (pintype "passive"))
      (node (ref "CM2") (pin "10") (pinfunction "10_10") (pintype "passive"))
      (node (ref "U1") (pin "14") (pinfunction "PTA1_14") (pintype "bidirectional"))
    )
    (net (code "24") (name "/UART0_TX") (class "Default")
      (node (ref "CF1") (pin "P$15") (pinfunction "15_P$15") (pintype "passive"))
      (node (ref "CF1") (pin "P$16") (pinfunction "16_P$16") (pintype "passive"))
      (node (ref "CM2") (pin "11") (pinfunction "11_11") (pintype "passive"))
      (node (ref "U1") (pin "13") (pinfunction "PTA2_13") (pintype "bidirectional"))
    )
    (net (code "25") (name "/VBIAS") (class "Default")
      (node (ref "C24") (pin "1") (pinfunction "1_1") (pintype "passive"))
      (node (ref "C38") (pin "2") (pinfunction "2_2") (pintype "passive"))
      (node (ref "C43") (pin "+") (pinfunction "+_+") (pintype "passive"))
      (node (ref "C44") (pin "1") (pinfunction "1_1") (pintype "passive"))
      (node (ref "L8") (pin "2") (pinfunction "2_2") (pintype "passive"))
      (node (ref "R1") (pin "2") (pinfunction "2_2") (pintype "passive"))
      (node (ref "R6") (pin "2") (pinfunction "2_2") (pintype "passive"))
      (node (ref "U$49") (pin "VDD") (pinfunction "VDD_VDD") (pintype "power_in"))
      (node (ref "U6") (pin "5") (pinfunction "VOUT_5") (pintype "power_in"))
    )
    (net (code "26") (name "/VPA") (class "Default")
      (node (ref "C15") (pin "2") (pinfunction "2_2") (pintype "passive"))
      (node (ref "C16") (pin "2") (pinfunction "2_2") (pintype "passive"))
      (node (ref "C17") (pin "2") (pinfunction "2_2") (pintype "passive"))
      (node (ref "C18") (pin "2") (pinfunction "2_2") (pintype "passive"))
      (node (ref "C19") (pin "2") (pinfunction "2_2") (pintype "passive"))
      (node (ref "C20") (pin "2") (pinfunction "2_2") (pintype "passive"))
      (node (ref "C21") (pin "2") (pinfunction "2_2") (pintype "passive"))
      (node (ref "C22") (pin "2") (pinfunction "2_2") (pintype "passive"))
      (node (ref "C46") (pin "2") (pinfunction "2_2") (pintype "passive"))
      (node (ref "R7") (pin "2") (pinfunction "2_2") (pintype "passive"))
      (node (ref "U2") (pin "10") (pinfunction "VCC2_10") (pintype "power_in"))
      (node (ref "U2") (pin "11") (pinfunction "VCNT_11") (pintype "power_in"))
      (node (ref "U2") (pin "12") (pinfunction "VREF_12") (pintype "power_in"))
      (node (ref "U2") (pin "4") (pinfunction "VCC1_4") (pintype "power_in"))
      (node (ref "U7") (pin "1") (pinfunction "OUT_1") (pintype "power_in"))
      (node (ref "U7") (pin "2") (pinfunction "ADJ_2") (pintype "passive"))
    )
    (net (code "27") (name "/VR_PA") (class "Default")
      (node (ref "C1") (pin "2") (pinfunction "2_2") (pintype "passive"))
      (node (ref "C3") (pin "1") (pinfunction "1_1") (pintype "passive"))
      (node (ref "L1") (pin "1") (pinfunction "1_1") (pintype "passive"))
      (node (ref "L2") (pin "1") (pinfunction "1_1") (pintype "passive"))
      (node (ref "U1") (pin "42") (pinfunction "VR_PA_42") (pintype "output"))
    )
    (net (code "28") (name "/~{CS}") (class "Default")
      (node (ref "!CS") (pin "1") (pinfunction "1_1") (pintype "passive"))
      (node (ref "U1") (pin "27") (pinfunction "PTD4_27") (pintype "bidirectional"))
      (node (ref "U3") (pin "1") (pinfunction "~{CS}_1") (pintype "input"))
    )
    (net (code "29") (name "/~{RESET}") (class "Default")
      (node (ref "!RESET") (pin "1") (pinfunction "1_1") (pintype "passive"))
      (node (ref "CM1") (pin "10") (pinfunction "SRST_10") (pintype "passive"))
      (node (ref "U1") (pin "33") (pinfunction "PTA20/~{RESET}_33") (pintype "bidirectional"))
    )
    (net (code "30") (name "3.3V") (class "Default")
      (node (ref "C26") (pin "1") (pinfunction "1_1") (pintype "passive"))
      (node (ref "C27") (pin "1") (pinfunction "1_1") (pintype "passive"))
      (node (ref "C28") (pin "2") (pinfunction "2_2") (pintype "passive"))
      (node (ref "C29") (pin "2") (pinfunction "2_2") (pintype "passive"))
      (node (ref "C30") (pin "2") (pinfunction "2_2") (pintype "passive"))
      (node (ref "C31") (pin "2") (pinfunction "2_2") (pintype "passive"))
      (node (ref "C41") (pin "2") (pinfunction "2_2") (pintype "passive"))
      (node (ref "C42") (pin "2") (pinfunction "2_2") (pintype "passive"))
      (node (ref "C53") (pin "1") (pinfunction "1_1") (pintype "passive"))
      (node (ref "CM1") (pin "1") (pinfunction "VDD_1") (pintype "passive"))
      (node (ref "CM2") (pin "2") (pinfunction "2_2") (pintype "passive"))
      (node (ref "R2") (pin "2") (pinfunction "2_2") (pintype "passive"))
      (node (ref "R3") (pin "2") (pinfunction "2_2") (pintype "passive"))
      (node (ref "R8") (pin "2") (pinfunction "2_2") (pintype "passive"))
      (node (ref "U1") (pin "1") (pinfunction "VREFH_1") (pintype "input"))
      (node (ref "U1") (pin "19") (pinfunction "VDD_19") (pintype "power_in"))
      (node (ref "U1") (pin "35") (pinfunction "VBAT2_35") (pintype "power_in"))
      (node (ref "U1") (pin "43") (pinfunction "VBAT1_43") (pintype "power_in"))
      (node (ref "U1") (pin "55") (pinfunction "VDD2_55") (pintype "power_in"))
      (node (ref "U1") (pin "56") (pinfunction "VDDA_56") (pintype "power_in"))
      (node (ref "U3") (pin "8") (pinfunction "VDD_8") (pintype "power_in"))
      (node (ref "U4") (pin "5") (pinfunction "VOUT_5") (pintype "power_in"))
    )
    (net (code "31") (name "DC_OUT") (class "Default")
      (node (ref "CF2") (pin "CENTER") (pinfunction "CENTER_CENTER") (pintype "passive"))
      (node (ref "U$22") (pin "OUT") (pinfunction "OUT_OUT") (pintype "bidirectional"))
    )
    (net (code "32") (name "GND") (class "Default")
      (node (ref "C26") (pin "2") (pinfunction "2_2") (pintype "passive"))
      (node (ref "C27") (pin "2") (pinfunction "2_2") (pintype "passive"))
      (node (ref "C28") (pin "1") (pinfunction "1_1") (pintype "passive"))
      (node (ref "C29") (pin "1") (pinfunction "1_1") (pintype "passive"))
      (node (ref "C34") (pin "1") (pinfunction "1_1") (pintype "passive"))
      (node (ref "C35") (pin "1") (pinfunction "1_1") (pintype "passive"))
      (node (ref "C39") (pin "1") (pinfunction "1_1") (pintype "passive"))
      (node (ref "C40") (pin "1") (pinfunction "1_1") (pintype "passive"))
      (node (ref "C41") (pin "1") (pinfunction "1_1") (pintype "passive"))
      (node (ref "C42") (pin "1") (pinfunction "1_1") (pintype "passive"))
      (node (ref "C52") (pin "2") (pinfunction "2_2") (pintype "passive"))
      (node (ref "C53") (pin "2") (pinfunction "2_2") (pintype "passive"))
      (node (ref "CF1") (pin "P$37") (pinfunction "37_P$37") (pintype "passive"))
      (node (ref "CF1") (pin "P$38") (pinfunction "38_P$38") (pintype "passive"))
      (node (ref "CF1") (pin "P$39") (pinfunction "39_P$39") (pintype "passive"))
      (node (ref "CF1") (pin "P$40") (pinfunction "40_P$40") (pintype "passive"))
      (node (ref "CM1") (pin "3") (pinfunction "GND3_3") (pintype "passive"))
      (node (ref "CM1") (pin "5") (pinfunction "GND5_5") (pintype "passive"))
      (node (ref "CM1") (pin "9") (pinfunction "GND9_9") (pintype "passive"))
      (node (ref "CM2") (pin "12") (pinfunction "12_12") (pintype "passive"))
      (node (ref "LED1") (pin "K") (pinfunction "K_K") (pintype "passive"))
      (node (ref "LED2") (pin "K") (pinfunction "K_K") (pintype "passive"))
      (node (ref "LED3") (pin "K") (pinfunction "K_K") (pintype "passive"))
      (node (ref "LED4") (pin "K") (pinfunction "K_K") (pintype "passive"))
      (node (ref "LED5") (pin "K") (pinfunction "K_K") (pintype "passive"))
      (node (ref "LED6") (pin "K") (pinfunction "K_K") (pintype "passive"))
      (node (ref "LED7") (pin "K") (pinfunction "K_K") (pintype "passive"))
      (node (ref "LED8") (pin "K") (pinfunction "K_K") (pintype "passive"))
      (node (ref "U1") (pin "2") (pinfunction "VREFL_2") (pintype "input"))
      (node (ref "U1") (pin "20") (pinfunction "VSS2_20") (pintype "power_in"))
      (node (ref "U1") (pin "3") (pinfunction "VSSA_3") (pintype "power_in"))
      (node (ref "U1") (pin "4") (pinfunction "VSS_4") (pintype "power_in"))
      (node (ref "U1") (pin "PGND2") (pinfunction "GND2_PGND2") (pintype "power_in"))
      (node (ref "U3") (pin "4") (pinfunction "GND_4") (pintype "power_in"))
      (node (ref "U4") (pin "2") (pinfunction "GND_2") (pintype "power_in"))
    )
    (net (code "33") (name "LNA_EN") (class "Default")
      (node (ref "C48") (pin "2") (pinfunction "2_2") (pintype "passive"))
      (node (ref "U1") (pin "17") (pinfunction "PTB0_17") (pintype "bidirectional"))
      (node (ref "U6") (pin "3") (pinfunction "EN_3") (pintype "input"))
    )
    (net (code "34") (name "Net-(C5-Pad2)") (class "Default")
      (node (ref "C5") (pin "2") (pinfunction "2_2") (pintype "passive"))
      (node (ref "C7") (pin "1") (pinfunction "1_1") (pintype "passive"))
      (node (ref "L3") (pin "1") (pinfunction "1_1") (pintype "passive"))
    )
    (net (code "35") (name "Net-(C6-Pad2)") (class "Default")
      (node (ref "C6") (pin "2") (pinfunction "2_2") (pintype "passive"))
      (node (ref "C8") (pin "1") (pinfunction "1_1") (pintype "passive"))
      (node (ref "L4") (pin "1") (pinfunction "1_1") (pintype "passive"))
    )
    (net (code "36") (name "Net-(C7-Pad2)") (class "Default")
      (node (ref "C7") (pin "2") (pinfunction "2_2") (pintype "passive"))
      (node (ref "C9") (pin "2") (pinfunction "2_2") (pintype "passive"))
      (node (ref "L3") (pin "2") (pinfunction "2_2") (pintype "passive"))
      (node (ref "L5") (pin "1") (pinfunction "1_1") (pintype "passive"))
    )
    (net (code "37") (name "Net-(C10-Pad2)") (class "Default")
      (node (ref "C10") (pin "2") (pinfunction "2_2") (pintype "passive"))
      (node (ref "C8") (pin "2") (pinfunction "2_2") (pintype "passive"))
      (node (ref "L4") (pin "2") (pinfunction "2_2") (pintype "passive"))
      (node (ref "L6") (pin "1") (pinfunction "1_1") (pintype "passive"))
    )
    (net (code "38") (name "Net-(C11-Pad2)") (class "Default")
      (node (ref "C11") (pin "2") (pinfunction "2_2") (pintype "passive"))
      (node (ref "C14") (pin "2") (pinfunction "2_2") (pintype "passive"))
      (node (ref "L5") (pin "2") (pinfunction "2_2") (pintype "passive"))
    )
    (net (code "39") (name "Net-(C45-Pad2)") (class "Default")
      (node (ref "C45") (pin "2") (pinfunction "2_2") (pintype "passive"))
      (node (ref "C50") (pin "2") (pinfunction "2_2") (pintype "passive"))
      (node (ref "R13") (pin "2") (pinfunction "2_2") (pintype "passive"))
      (node (ref "R7") (pin "1") (pinfunction "1_1") (pintype "passive"))
    )
    (net (code "40") (name "Net-(C47-Pad2)") (class "Default")
      (node (ref "C47") (pin "2") (pinfunction "2_2") (pintype "passive"))
      (node (ref "C51") (pin "2") (pinfunction "2_2") (pintype "passive"))
      (node (ref "R14") (pin "2") (pinfunction "2_2") (pintype "passive"))
      (node (ref "R6") (pin "1") (pinfunction "1_1") (pintype "passive"))
    )
    (net (code "41") (name "Net-(C49-Pad1)") (class "Default")
      (node (ref "C49") (pin "1") (pinfunction "1_1") (pintype "passive"))
      (node (ref "D1") (pin "C") (pinfunction "C_C") (pintype "passive"))
      (node (ref "R20") (pin "2") (pinfunction "2_2") (pintype "passive"))
    )
    (net (code "42") (name "Net-(C57-Pad1)") (class "Default")
      (node (ref "C57") (pin "1") (pinfunction "1_1") (pintype "passive"))
      (node (ref "D2") (pin "C") (pinfunction "C_C") (pintype "passive"))
      (node (ref "R21") (pin "2") (pinfunction "2_2") (pintype "passive"))
    )
    (net (code "43") (name "Net-(C61-Pad1)") (class "Default")
      (node (ref "C61") (pin "1") (pinfunction "1_1") (pintype "passive"))
      (node (ref "U$49") (pin "RFC") (pinfunction "RFC_RFC") (pintype "bidirectional"))
    )
    (net (code "44") (name "Net-(CM2-Pad9)") (class "Default")
      (node (ref "CM2") (pin "9") (pinfunction "9_9") (pintype "passive"))
      (node (ref "TP1") (pin "1") (pinfunction "1_1") (pintype "passive"))
    )
    (net (code "45") (name "Net-(LED1-PadA)") (class "Default")
      (node (ref "LED1") (pin "A") (pinfunction "A_A") (pintype "passive"))
      (node (ref "R4") (pin "1") (pinfunction "1_1") (pintype "passive"))
    )
    (net (code "46") (name "Net-(LED2-PadA)") (class "Default")
      (node (ref "LED2") (pin "A") (pinfunction "A_A") (pintype "passive"))
      (node (ref "R14") (pin "1") (pinfunction "1_1") (pintype "passive"))
    )
    (net (code "47") (name "Net-(LED3-PadA)") (class "Default")
      (node (ref "LED3") (pin "A") (pinfunction "A_A") (pintype "passive"))
      (node (ref "R13") (pin "1") (pinfunction "1_1") (pintype "passive"))
    )
    (net (code "48") (name "Net-(LED4-PadA)") (class "Default")
      (node (ref "LED4") (pin "A") (pinfunction "A_A") (pintype "passive"))
      (node (ref "R8") (pin "1") (pinfunction "1_1") (pintype "passive"))
    )
    (net (code "49") (name "Net-(LED5-PadA)") (class "Default")
      (node (ref "LED5") (pin "A") (pinfunction "A_A") (pintype "passive"))
      (node (ref "R9") (pin "1") (pinfunction "1_1") (pintype "passive"))
    )
    (net (code "50") (name "Net-(LED6-PadA)") (class "Default")
      (node (ref "LED6") (pin "A") (pinfunction "A_A") (pintype "passive"))
      (node (ref "R10") (pin "1") (pinfunction "1_1") (pintype "passive"))
    )
    (net (code "51") (name "Net-(LED7-PadA)") (class "Default")
      (node (ref "LED7") (pin "A") (pinfunction "A_A") (pintype "passive"))
      (node (ref "R11") (pin "1") (pinfunction "1_1") (pintype "passive"))
    )
    (net (code "52") (name "Net-(LED8-PadA)") (class "Default")
      (node (ref "LED8") (pin "A") (pinfunction "A_A") (pintype "passive"))
      (node (ref "R12") (pin "1") (pinfunction "1_1") (pintype "passive"))
    )
    (net (code "53") (name "Net-(U1-DIO2)") (class "Default")
      (node (ref "DIO2") (pin "1") (pinfunction "1_1") (pintype "passive"))
      (node (ref "U1") (pin "51") (pinfunction "DIO2_51") (pintype "bidirectional"))
    )
    (net (code "54") (name "Net-(U1-DIO3)") (class "Default")
      (node (ref "DIO3") (pin "1") (pinfunction "1_1") (pintype "passive"))
      (node (ref "U1") (pin "52") (pinfunction "DIO3_52") (pintype "bidirectional"))
    )
    (net (code "55") (name "Net-(U1-DIO4)") (class "Default")
      (node (ref "DIO4") (pin "1") (pinfunction "1_1") (pintype "passive"))
      (node (ref "U1") (pin "53") (pinfunction "DIO4_53") (pintype "bidirectional"))
    )
    (net (code "56") (name "Net-(U1-PTE16)") (class "Default")
      (node (ref "RF-RESET") (pin "1") (pinfunction "1_1") (pintype "passive"))
      (node (ref "U1") (pin "48") (pinfunction "RESET(RF)_48") (pintype "input"))
      (node (ref "U1") (pin "5") (pinfunction "PTE16_5") (pintype "bidirectional"))
    )
    (net (code "57") (name "Net-(U1-VR_ANA)") (class "Default")
      (node (ref "C32") (pin "2") (pinfunction "2_2") (pintype "passive"))
      (node (ref "U1") (pin "44") (pinfunction "VR_ANA_44") (pintype "output"))
    )
    (net (code "58") (name "Net-(U1-VR_DIG)") (class "Default")
      (node (ref "C33") (pin "2") (pinfunction "2_2") (pintype "passive"))
      (node (ref "U1") (pin "45") (pinfunction "VR_DIG_45") (pintype "output"))
    )
    (net (code "59") (name "Net-(U1-XTA)") (class "Default")
      (node (ref "C34") (pin "2") (pinfunction "2_2") (pintype "passive"))
      (node (ref "U1") (pin "46") (pinfunction "XTA_46") (pintype "passive"))
      (node (ref "XTAL") (pin "1") (pinfunction "1_1") (pintype "passive"))
      (node (ref "Y1") (pin "1") (pinfunction "1_1") (pintype "passive"))
    )
    (net (code "60") (name "Net-(U1-XTB)") (class "Default")
      (node (ref "C35") (pin "2") (pinfunction "2_2") (pintype "passive"))
      (node (ref "U1") (pin "47") (pinfunction "XTB_47") (pintype "passive"))
      (node (ref "Y1") (pin "3") (pinfunction "2_3") (pintype "passive"))
    )
    (net (code "61") (name "Net-(U2-RFIN)") (class "Default")
      (node (ref "C14") (pin "1") (pinfunction "1_1") (pintype "passive"))
      (node (ref "U2") (pin "2") (pinfunction "RFIN_2") (pintype "input"))
    )
    (net (code "62") (name "Net-(U2-RFOUT)") (class "Default")
      (node (ref "C58") (pin "1") (pinfunction "1_1") (pintype "passive"))
      (node (ref "U2") (pin "8") (pinfunction "RFOUT_8") (pintype "output"))
    )
    (net (code "63") (name "Net-(U3-~{HOLD})") (class "Default")
      (node (ref "!HOLD") (pin "1") (pinfunction "1_1") (pintype "passive"))
      (node (ref "R2") (pin "1") (pinfunction "1_1") (pintype "passive"))
      (node (ref "U3") (pin "7") (pinfunction "~{HOLD}_7") (pintype "input"))
    )
    (net (code "64") (name "Net-(U3-~{WP})") (class "Default")
      (node (ref "!WP") (pin "1") (pinfunction "1_1") (pintype "passive"))
      (node (ref "R3") (pin "1") (pinfunction "1_1") (pintype "passive"))
      (node (ref "U3") (pin "3") (pinfunction "~{WP}_3") (pintype "input"))
    )
    (net (code "65") (name "Net-(U4-BYP)") (class "Default")
      (node (ref "C40") (pin "2") (pinfunction "2_2") (pintype "passive"))
      (node (ref "U4") (pin "4") (pinfunction "BYP_4") (pintype "passive"))
    )
    (net (code "66") (name "Net-(U4-EN)") (class "Default")
      (node (ref "LDO_EN") (pin "1") (pinfunction "1_1") (pintype "passive"))
      (node (ref "R5") (pin "1") (pinfunction "1_1") (pintype "passive"))
      (node (ref "U4") (pin "3") (pinfunction "EN_3") (pintype "input"))
    )
    (net (code "67") (name "Net-(U4-VIN)") (class "Default")
      (node (ref "C39") (pin "2") (pinfunction "2_2") (pintype "passive"))
      (node (ref "R15") (pin "1") (pinfunction "1_1") (pintype "passive"))
      (node (ref "R5") (pin "2") (pinfunction "2_2") (pintype "passive"))
      (node (ref "U4") (pin "1") (pinfunction "VIN_1") (pintype "power_in"))
    )
    (net (code "68") (name "Net-(U6-BYP)") (class "Default")
      (node (ref "C37") (pin "2") (pinfunction "2_2") (pintype "passive"))
      (node (ref "U6") (pin "4") (pinfunction "BYP_4") (pintype "passive"))
    )
    (net (code "69") (name "Net-(U6-VIN)") (class "Default")
      (node (ref "C36") (pin "2") (pinfunction "2_2") (pintype "passive"))
      (node (ref "R17") (pin "1") (pinfunction "1_1") (pintype "passive"))
      (node (ref "U6") (pin "1") (pinfunction "VIN_1") (pintype "power_in"))
    )
    (net (code "70") (name "Net-(U7-IN)") (class "Default")
      (node (ref "C13") (pin "2") (pinfunction "2_2") (pintype "passive"))
      (node (ref "R16") (pin "1") (pinfunction "1_1") (pintype "passive"))
      (node (ref "U7") (pin "6") (pinfunction "IN_6") (pintype "power_in"))
    )
    (net (code "71") (name "Net-(U7-PG)") (class "Default")
      (node (ref "PG") (pin "1") (pinfunction "1_1") (pintype "passive"))
      (node (ref "U7") (pin "4") (pinfunction "PG_4") (pintype "open_collector"))
    )
    (net (code "72") (name "Net-(U8-RFIN)") (class "Default")
      (node (ref "C23") (pin "1") (pinfunction "1_1") (pintype "passive"))
      (node (ref "U8") (pin "3") (pinfunction "RFIN_3") (pintype "input"))
    )
    (net (code "73") (name "Net-(U8-RFOUT)") (class "Default")
      (node (ref "C25") (pin "2") (pinfunction "2_2") (pintype "passive"))
      (node (ref "L8") (pin "1") (pinfunction "1_1") (pintype "passive"))
      (node (ref "U8") (pin "6") (pinfunction "RFOUT_6") (pintype "output"))
    )
    (net (code "74") (name "Net-(U8-VBIAS)") (class "Default")
      (node (ref "R1") (pin "1") (pinfunction "1_1") (pintype "passive"))
      (node (ref "U8") (pin "4") (pinfunction "VBIAS_4") (pintype "power_in"))
    )
    (net (code "75") (name "PA_EN") (class "Default")
      (node (ref "U1") (pin "18") (pinfunction "PTB1_18") (pintype "bidirectional"))
      (node (ref "U7") (pin "5") (pinfunction "EN_5") (pintype "input"))
    )
    (net (code "76") (name "RFC") (class "Default")
      (node (ref "C61") (pin "2") (pinfunction "2_2") (pintype "passive"))
      (node (ref "U$22") (pin "IN") (pinfunction "IN_IN") (pintype "bidirectional"))
    )
    (net (code "77") (name "RF_GND") (class "Default")
      (node (ref "C1") (pin "1") (pinfunction "1_1") (pintype "passive"))
      (node (ref "C10") (pin "1") (pinfunction "1_1") (pintype "passive"))
      (node (ref "C11") (pin "1") (pinfunction "1_1") (pintype "passive"))
      (node (ref "C12") (pin "1") (pinfunction "1_1") (pintype "passive"))
      (node (ref "C13") (pin "1") (pinfunction "1_1") (pintype "passive"))
      (node (ref "C15") (pin "1") (pinfunction "1_1") (pintype "passive"))
      (node (ref "C16") (pin "1") (pinfunction "1_1") (pintype "passive"))
      (node (ref "C17") (pin "1") (pinfunction "1_1") (pintype "passive"))
      (node (ref "C18") (pin "1") (pinfunction "1_1") (pintype "passive"))
      (node (ref "C19") (pin "1") (pinfunction "1_1") (pintype "passive"))
      (node (ref "C2") (pin "2") (pinfunction "2_2") (pintype "passive"))
      (node (ref "C20") (pin "1") (pinfunction "1_1") (pintype "passive"))
      (node (ref "C21") (pin "1") (pinfunction "1_1") (pintype "passive"))
      (node (ref "C22") (pin "1") (pinfunction "1_1") (pintype "passive"))
      (node (ref "C24") (pin "2") (pinfunction "2_2") (pintype "passive"))
      (node (ref "C3") (pin "2") (pinfunction "2_2") (pintype "passive"))
      (node (ref "C30") (pin "1") (pinfunction "1_1") (pintype "passive"))
      (node (ref "C31") (pin "1") (pinfunction "1_1") (pintype "passive"))
      (node (ref "C32") (pin "1") (pinfunction "1_1") (pintype "passive"))
      (node (ref "C33") (pin "1") (pinfunction "1_1") (pintype "passive"))
      (node (ref "C36") (pin "1") (pinfunction "1_1") (pintype "passive"))
      (node (ref "C37") (pin "1") (pinfunction "1_1") (pintype "passive"))
      (node (ref "C38") (pin "1") (pinfunction "1_1") (pintype "passive"))
      (node (ref "C4") (pin "2") (pinfunction "2_2") (pintype "passive"))
      (node (ref "C43") (pin "-") (pinfunction "-_-") (pintype "passive"))
      (node (ref "C44") (pin "2") (pinfunction "2_2") (pintype "passive"))
      (node (ref "C45") (pin "1") (pinfunction "1_1") (pintype "passive"))
      (node (ref "C46") (pin "1") (pinfunction "1_1") (pintype "passive"))
      (node (ref "C47") (pin "1") (pinfunction "1_1") (pintype "passive"))
      (node (ref "C48") (pin "1") (pinfunction "1_1") (pintype "passive"))
      (node (ref "C49") (pin "2") (pinfunction "2_2") (pintype "passive"))
      (node (ref "C50") (pin "1") (pinfunction "1_1") (pintype "passive"))
      (node (ref "C51") (pin "1") (pinfunction "1_1") (pintype "passive"))
      (node (ref "C54") (pin "1") (pinfunction "1_1") (pintype "passive"))
      (node (ref "C55") (pin "2") (pinfunction "2_2") (pintype "passive"))
      (node (ref "C56") (pin "2") (pinfunction "2_2") (pintype "passive"))
      (node (ref "C57") (pin "2") (pinfunction "2_2") (pintype "passive"))
      (node (ref "C60") (pin "1") (pinfunction "1_1") (pintype "passive"))
      (node (ref "C9") (pin "1") (pinfunction "1_1") (pintype "passive"))
      (node (ref "CF2") (pin "G1") (pinfunction "SHIELD_G1") (pintype "passive"))
      (node (ref "CF2") (pin "G2") (pinfunction "SHIELD_G2") (pintype "passive"))
      (node (ref "CF2") (pin "G3") (pinfunction "SHIELD_G3") (pintype "passive"))
      (node (ref "CF2") (pin "G4") (pinfunction "SHIELD_G4") (pintype "passive"))
      (node (ref "R18") (pin "1") (pinfunction "1_1") (pintype "passive"))
      (node (ref "R19") (pin "1") (pinfunction "1_1") (pintype "passive"))
      (node (ref "SH1") (pin "P$1") (pinfunction "P$1_P$1") (pintype "power_in"))
      (node (ref "SH1") (pin "P$10") (pinfunction "P$1_P$10") (pintype "power_in"))
      (node (ref "SH1") (pin "P$11") (pinfunction "P$1_P$11") (pintype "power_in"))
      (node (ref "SH1") (pin "P$12") (pinfunction "P$1_P$12") (pintype "power_in"))
      (node (ref "SH1") (pin "P$2") (pinfunction "P$1_P$2") (pintype "power_in"))
      (node (ref "SH1") (pin "P$3") (pinfunction "P$1_P$3") (pintype "power_in"))
      (node (ref "SH1") (pin "P$4") (pinfunction "P$1_P$4") (pintype "power_in"))
      (node (ref "SH1") (pin "P$5") (pinfunction "P$1_P$5") (pintype "power_in"))
      (node (ref "SH1") (pin "P$6") (pinfunction "P$1_P$6") (pintype "power_in"))
      (node (ref "SH1") (pin "P$7") (pinfunction "P$1_P$7") (pintype "power_in"))
      (node (ref "SH1") (pin "P$8") (pinfunction "P$1_P$8") (pintype "power_in"))
      (node (ref "SH1") (pin "P$9") (pinfunction "P$1_P$9") (pintype "power_in"))
      (node (ref "SH2") (pin "P$1") (pinfunction "P$1_P$1") (pintype "power_in"))
      (node (ref "SH2") (pin "P$10") (pinfunction "P$1_P$10") (pintype "power_in"))
      (node (ref "SH2") (pin "P$11") (pinfunction "P$1_P$11") (pintype "power_in"))
      (node (ref "SH2") (pin "P$12") (pinfunction "P$1_P$12") (pintype "power_in"))
      (node (ref "SH2") (pin "P$2") (pinfunction "P$1_P$2") (pintype "power_in"))
      (node (ref "SH2") (pin "P$3") (pinfunction "P$1_P$3") (pintype "power_in"))
      (node (ref "SH2") (pin "P$4") (pinfunction "P$1_P$4") (pintype "power_in"))
      (node (ref "SH2") (pin "P$5") (pinfunction "P$1_P$5") (pintype "power_in"))
      (node (ref "SH2") (pin "P$6") (pinfunction "P$1_P$6") (pintype "power_in"))
      (node (ref "SH2") (pin "P$7") (pinfunction "P$1_P$7") (pintype "power_in"))
      (node (ref "SH2") (pin "P$8") (pinfunction "P$1_P$8") (pintype "power_in"))
      (node (ref "SH2") (pin "P$9") (pinfunction "P$1_P$9") (pintype "power_in"))
      (node (ref "U$22") (pin "GND") (pinfunction "GND_GND") (pintype "power_in"))
      (node (ref "U$22") (pin "GND2") (pinfunction "GND2_GND2") (pintype "power_in"))
      (node (ref "U$49") (pin "GND") (pinfunction "GND_GND") (pintype "power_in"))
      (node (ref "U$49") (pin "GND1") (pinfunction "GND1_GND1") (pintype "power_in"))
      (node (ref "U$49") (pin "GND10") (pinfunction "GND10_GND10") (pintype "power_in"))
      (node (ref "U$49") (pin "GND2") (pinfunction "GND2_GND2") (pintype "power_in"))
      (node (ref "U$49") (pin "GND3") (pinfunction "GND3_GND3") (pintype "power_in"))
      (node (ref "U$49") (pin "GND4") (pinfunction "GND4_GND4") (pintype "power_in"))
      (node (ref "U$49") (pin "GND5") (pinfunction "GND5_GND5") (pintype "power_in"))
      (node (ref "U$49") (pin "GND6") (pinfunction "GND6_GND6") (pintype "power_in"))
      (node (ref "U$49") (pin "GND7") (pinfunction "GND7_GND7") (pintype "power_in"))
      (node (ref "U$49") (pin "GND8") (pinfunction "GND8_GND8") (pintype "power_in"))
      (node (ref "U$49") (pin "GND9") (pinfunction "GND9_GND9") (pintype "power_in"))
      (node (ref "U$49") (pin "PADDLE") (pinfunction "PADDLE_PADDLE") (pintype "power_in"))
      (node (ref "U1") (pin "36") (pinfunction "GND/SCAN_36") (pintype "power_in"))
      (node (ref "U1") (pin "38") (pinfunction "GND_PA2_38") (pintype "power_in"))
      (node (ref "U1") (pin "40") (pinfunction "GND_PA1_40") (pintype "power_in"))
      (node (ref "U1") (pin "PGND1") (pinfunction "GND1_PGND1") (pintype "power_in"))
      (node (ref "U2") (pin "1") (pinfunction "GND_1") (pintype "power_in"))
      (node (ref "U2") (pin "3") (pinfunction "GND_3") (pintype "power_in"))
      (node (ref "U2") (pin "5") (pinfunction "GND_5") (pintype "power_in"))
      (node (ref "U2") (pin "6") (pinfunction "GND_6") (pintype "power_in"))
      (node (ref "U2") (pin "7") (pinfunction "GND_7") (pintype "power_in"))
      (node (ref "U2") (pin "9") (pinfunction "GND_9") (pintype "power_in"))
      (node (ref "U2") (pin "CENTER") (pinfunction "GND_CENTER") (pintype "power_in"))
      (node (ref "U6") (pin "2") (pinfunction "GND_2") (pintype "power_in"))
      (node (ref "U7") (pin "3") (pinfunction "GND_3") (pintype "power_in"))
      (node (ref "U7") (pin "CENTER") (pinfunction "GND_CENTER") (pintype "power_in"))
      (node (ref "U8") (pin "1") (pinfunction "NC_1") (pintype "passive"))
      (node (ref "U8") (pin "2") (pinfunction "GND_2") (pintype "power_in"))
      (node (ref "U8") (pin "5") (pinfunction "GND_5") (pintype "power_in"))
    )
    (net (code "78") (name "V+") (class "Default")
      (node (ref "C52") (pin "1") (pinfunction "1_1") (pintype "passive"))
      (node (ref "C54") (pin "2") (pinfunction "2_2") (pintype "passive"))
      (node (ref "CF1") (pin "P$33") (pinfunction "33_P$33") (pintype "passive"))
      (node (ref "CF1") (pin "P$34") (pinfunction "34_P$34") (pintype "passive"))
      (node (ref "CF1") (pin "P$35") (pinfunction "35_P$35") (pintype "passive"))
      (node (ref "CF1") (pin "P$36") (pinfunction "36_P$36") (pintype "passive"))
      (node (ref "CM2") (pin "1") (pinfunction "1_1") (pintype "passive"))
      (node (ref "R15") (pin "2") (pinfunction "2_2") (pintype "passive"))
      (node (ref "R16") (pin "2") (pinfunction "2_2") (pintype "passive"))
      (node (ref "R17") (pin "2") (pinfunction "2_2") (pintype "passive"))
      (node (ref "R4") (pin "2") (pinfunction "2_2") (pintype "passive"))
    )
    (net (code "79") (name "VFWD") (class "Default")
      (node (ref "C56") (pin "1") (pinfunction "1_1") (pintype "passive"))
      (node (ref "R21") (pin "1") (pinfunction "1_1") (pintype "passive"))
      (node (ref "U1") (pin "6") (pinfunction "PTE17_6") (pintype "bidirectional"))
    )
    (net (code "80") (name "VREV") (class "Default")
      (node (ref "C55") (pin "1") (pinfunction "1_1") (pintype "passive"))
      (node (ref "R20") (pin "1") (pinfunction "1_1") (pintype "passive"))
      (node (ref "U1") (pin "7") (pinfunction "PTE18_7") (pintype "bidirectional"))
    )
    (net (code "81") (name "unconnected-(CF1-1-PadP$1)") (class "Default")
      (node (ref "CF1") (pin "P$1") (pinfunction "1_P$1") (pintype "passive"))
    )
    (net (code "82") (name "unconnected-(CF1-2-PadP$2)") (class "Default")
      (node (ref "CF1") (pin "P$2") (pinfunction "2_P$2") (pintype "passive"))
    )
    (net (code "83") (name "unconnected-(CF1-3-PadP$3)") (class "Default")
      (node (ref "CF1") (pin "P$3") (pinfunction "3_P$3") (pintype "passive"))
    )
    (net (code "84") (name "unconnected-(CF1-4-PadP$4)") (class "Default")
      (node (ref "CF1") (pin "P$4") (pinfunction "4_P$4") (pintype "passive"))
    )
    (net (code "85") (name "unconnected-(CF1-5-PadP$5)") (class "Default")
      (node (ref "CF1") (pin "P$5") (pinfunction "5_P$5") (pintype "passive"))
    )
    (net (code "86") (name "unconnected-(CF1-6-PadP$6)") (class "Default")
      (node (ref "CF1") (pin "P$6") (pinfunction "6_P$6") (pintype "passive"))
    )
    (net (code "87") (name "unconnected-(CF1-7-PadP$7)") (class "Default")
      (node (ref "CF1") (pin "P$7") (pinfunction "7_P$7") (pintype "passive"))
    )
    (net (code "88") (name "unconnected-(CF1-8-PadP$8)") (class "Default")
      (node (ref "CF1") (pin "P$8") (pinfunction "8_P$8") (pintype "passive"))
    )
    (net (code "89") (name "unconnected-(CF1-9-PadP$9)") (class "Default")
      (node (ref "CF1") (pin "P$9") (pinfunction "9_P$9") (pintype "passive"))
    )
    (net (code "90") (name "unconnected-(CF1-10-PadP$10)") (class "Default")
      (node (ref "CF1") (pin "P$10") (pinfunction "10_P$10") (pintype "passive"))
    )
    (net (code "91") (name "unconnected-(CF1-11-PadP$11)") (class "Default")
      (node (ref "CF1") (pin "P$11") (pinfunction "11_P$11") (pintype "passive"))
    )
    (net (code "92") (name "unconnected-(CF1-12-PadP$12)") (class "Default")
      (node (ref "CF1") (pin "P$12") (pinfunction "12_P$12") (pintype "passive"))
    )
    (net (code "93") (name "unconnected-(CF1-13-PadP$13)") (class "Default")
      (node (ref "CF1") (pin "P$13") (pinfunction "13_P$13") (pintype "passive"))
    )
    (net (code "94") (name "unconnected-(CF1-14-PadP$14)") (class "Default")
      (node (ref "CF1") (pin "P$14") (pinfunction "14_P$14") (pintype "passive"))
    )
    (net (code "95") (name "unconnected-(CF1-19-PadP$19)") (class "Default")
      (node (ref "CF1") (pin "P$19") (pinfunction "19_P$19") (pintype "passive"))
    )
    (net (code "96") (name "unconnected-(CF1-20-PadP$20)") (class "Default")
      (node (ref "CF1") (pin "P$20") (pinfunction "20_P$20") (pintype "passive"))
    )
    (net (code "97") (name "unconnected-(CF1-21-PadP$21)") (class "Default")
      (node (ref "CF1") (pin "P$21") (pinfunction "21_P$21") (pintype "passive"))
    )
    (net (code "98") (name "unconnected-(CF1-22-PadP$22)") (class "Default")
      (node (ref "CF1") (pin "P$22") (pinfunction "22_P$22") (pintype "passive"))
    )
    (net (code "99") (name "unconnected-(CF1-23-PadP$23)") (class "Default")
      (node (ref "CF1") (pin "P$23") (pinfunction "23_P$23") (pintype "passive"))
    )
    (net (code "100") (name "unconnected-(CF1-24-PadP$24)") (class "Default")
      (node (ref "CF1") (pin "P$24") (pinfunction "24_P$24") (pintype "passive"))
    )
    (net (code "101") (name "unconnected-(CF1-25-PadP$25)") (class "Default")
      (node (ref "CF1") (pin "P$25") (pinfunction "25_P$25") (pintype "passive"))
    )
    (net (code "102") (name "unconnected-(CF1-26-PadP$26)") (class "Default")
      (node (ref "CF1") (pin "P$26") (pinfunction "26_P$26") (pintype "passive"))
    )
    (net (code "103") (name "unconnected-(CF1-27-PadP$27)") (class "Default")
      (node (ref "CF1") (pin "P$27") (pinfunction "27_P$27") (pintype "passive"))
    )
    (net (code "104") (name "unconnected-(CF1-28-PadP$28)") (class "Default")
      (node (ref "CF1") (pin "P$28") (pinfunction "28_P$28") (pintype "passive"))
    )
    (net (code "105") (name "unconnected-(CF1-29-PadP$29)") (class "Default")
      (node (ref "CF1") (pin "P$29") (pinfunction "29_P$29") (pintype "passive"))
    )
    (net (code "106") (name "unconnected-(CF1-30-PadP$30)") (class "Default")
      (node (ref "CF1") (pin "P$30") (pinfunction "30_P$30") (pintype "passive"))
    )
    (net (code "107") (name "unconnected-(CF1-31-PadP$31)") (class "Default")
      (node (ref "CF1") (pin "P$31") (pinfunction "31_P$31") (pintype "passive"))
    )
    (net (code "108") (name "unconnected-(CF1-32-PadP$32)") (class "Default")
      (node (ref "CF1") (pin "P$32") (pinfunction "32_P$32") (pintype "passive"))
    )
    (net (code "109") (name "unconnected-(CM1-RTCK-Pad7)") (class "Default")
      (node (ref "CM1") (pin "7") (pinfunction "RTCK_7") (pintype "passive"))
    )
    (net (code "110") (name "unconnected-(CM1-TDI-Pad8)") (class "Default")
      (node (ref "CM1") (pin "8") (pinfunction "TDI_8") (pintype "passive"))
    )
    (net (code "111") (name "unconnected-(CM1-TDO-Pad6)") (class "Default")
      (node (ref "CM1") (pin "6") (pinfunction "TDO_6") (pintype "passive"))
    )
    (net (code "112") (name "unconnected-(U1-NC-Pad30)") (class "Default")
      (node (ref "U1") (pin "30") (pinfunction "NC_30") (pintype "no_connect"))
    )
    (net (code "113") (name "unconnected-(U1-PTA19{slash}XTAL0-Pad16)") (class "Default")
      (node (ref "U1") (pin "16") (pinfunction "PTA19/XTAL0_16") (pintype "bidirectional"))
    )
    (net (code "114") (name "unconnected-(U1-PTB2-Pad21)") (class "Default")
      (node (ref "U1") (pin "21") (pinfunction "PTB2_21") (pintype "bidirectional"))
    )
    (net (code "115") (name "unconnected-(U1-PTB17-Pad22)") (class "Default")
      (node (ref "U1") (pin "22") (pinfunction "PTB17_22") (pintype "bidirectional"))
    )
    (net (code "116") (name "unconnected-(U1-PTC5-Pad59)") (class "Default")
      (node (ref "U1") (pin "59") (pinfunction "PTC5_59") (pintype "bidirectional"))
    )
    (net (code "117") (name "unconnected-(U1-PTC6-Pad60)") (class "Default")
      (node (ref "U1") (pin "60") (pinfunction "PTC6_60") (pintype "bidirectional"))
    )
    (net (code "118") (name "unconnected-(U1-PTC7-Pad57)") (class "Default")
      (node (ref "U1") (pin "57") (pinfunction "PTC7_57") (pintype "bidirectional"))
    )
    (net (code "119") (name "unconnected-(U1-PTD0-Pad58)") (class "Default")
      (node (ref "U1") (pin "58") (pinfunction "PTD0_58") (pintype "bidirectional"))
    )
    (net (code "120") (name "unconnected-(U1-PTE0-Pad32)") (class "Default")
      (node (ref "U1") (pin "32") (pinfunction "PTE0_32") (pintype "bidirectional"))
    )
    (net (code "121") (name "unconnected-(U1-PTE1-Pad34)") (class "Default")
      (node (ref "U1") (pin "34") (pinfunction "PTE1_34") (pintype "bidirectional"))
    )
    (net (code "122") (name "unconnected-(U1-PTE19-Pad8)") (class "Default")
      (node (ref "U1") (pin "8") (pinfunction "PTE19_8") (pintype "bidirectional"))
    )
  )
)
